# Spring12_6_rev4.net
KiCad netlist of a schematic drawn in EAGLE
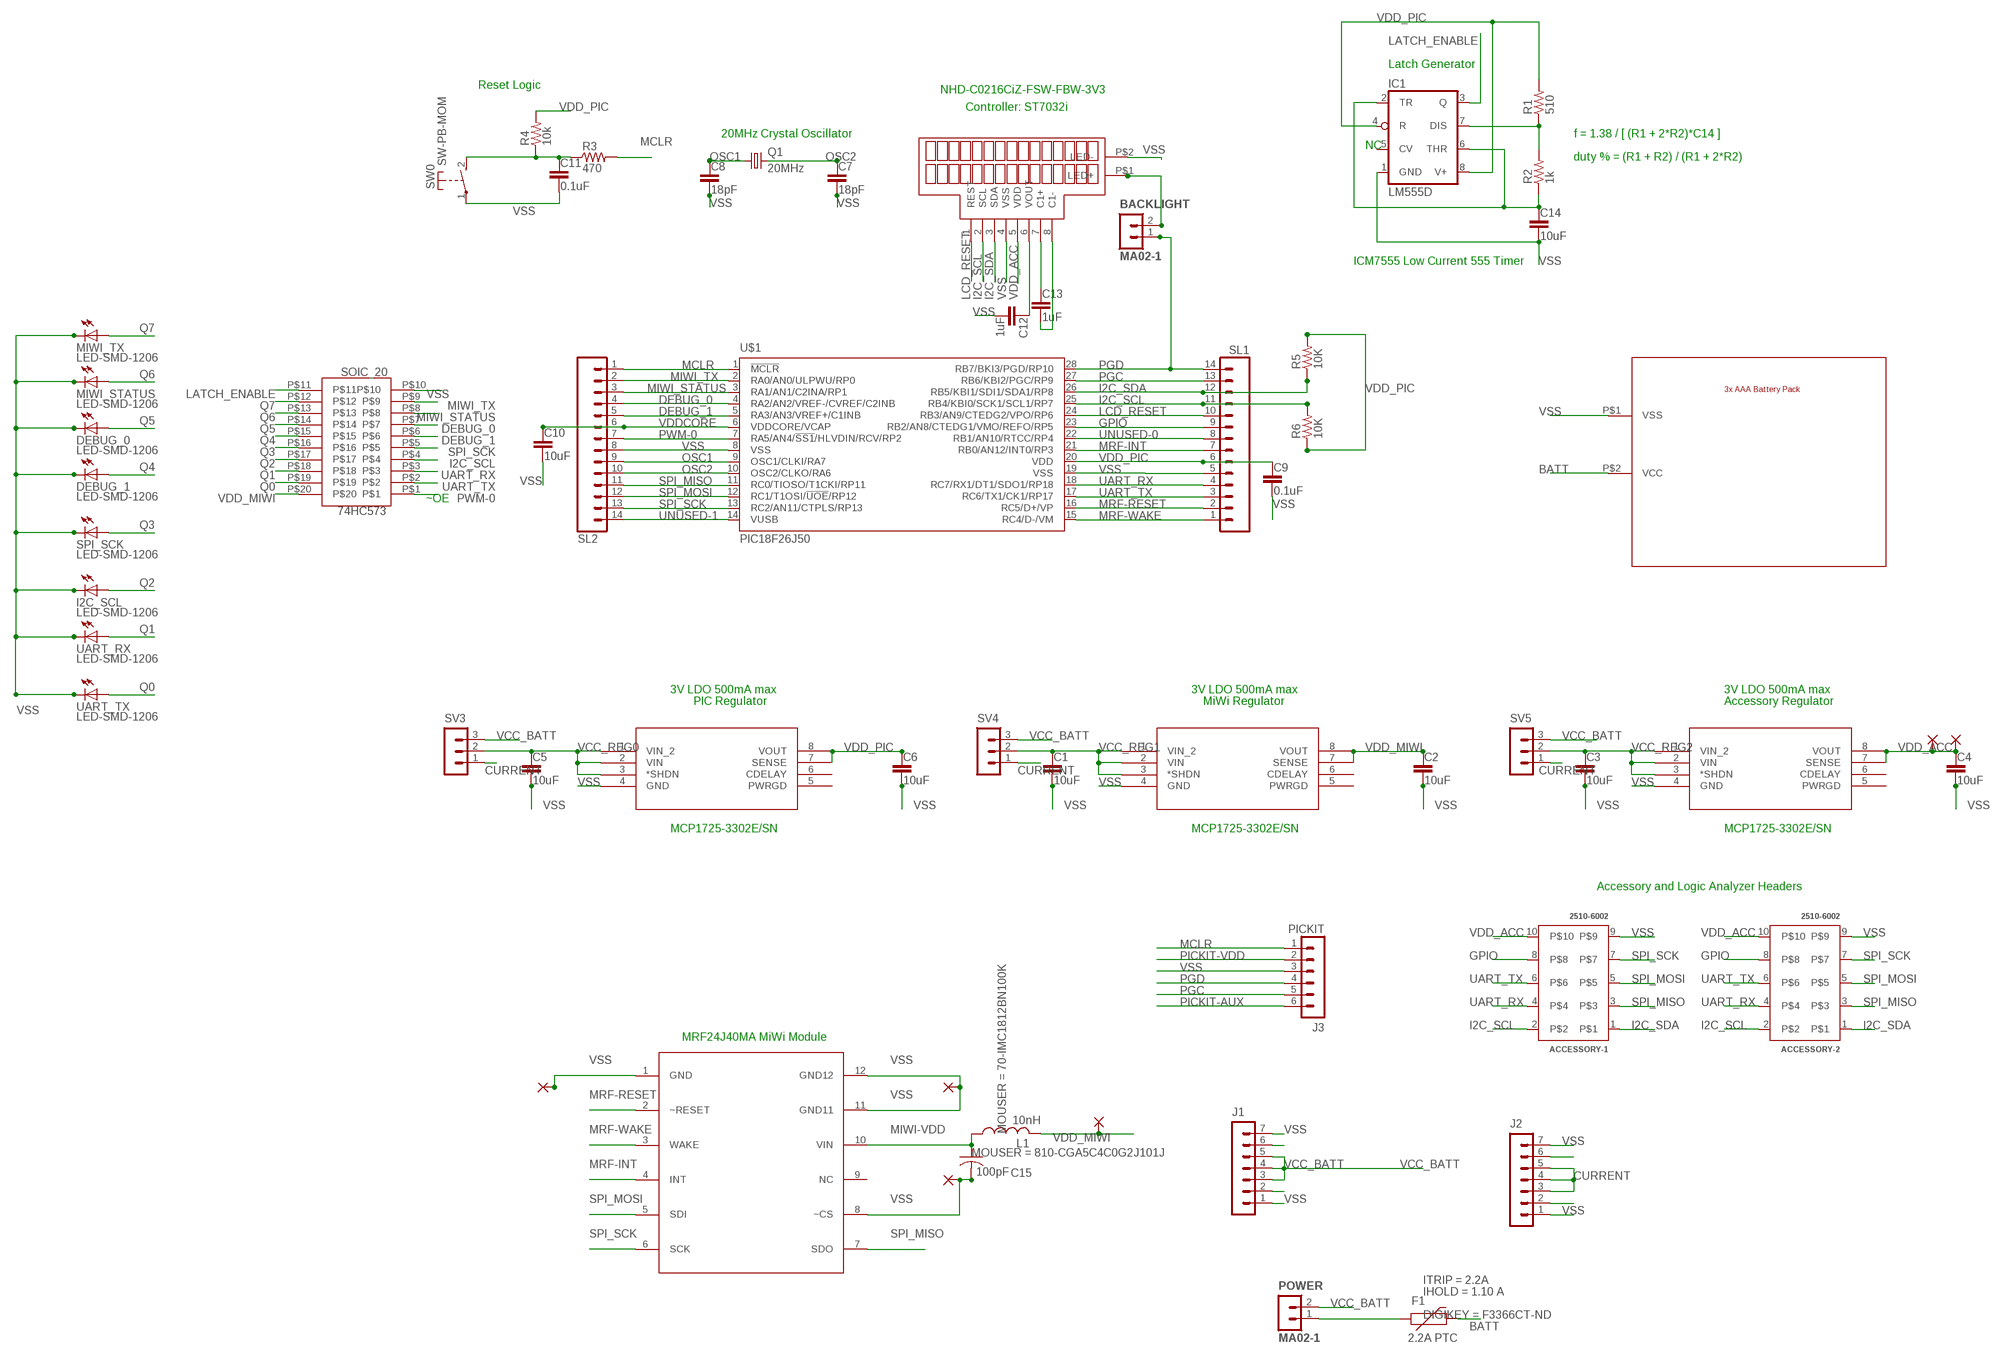
[diagram p0: schematic, sheet 1]

(export (version "E")
  (design (tool "Eeschema 10.0.6"))
  (components
    (comp (ref "74HC573")
      (value "SOIC_20")
      (footprint "eagle-import:SO20W")
      (libsource (lib "eagle-import") (part "SOIC_20"))
    )
    (comp (ref "ACCESSORY-1")
      (value "2510-6002")
      (footprint "eagle-import:2510-6002")
      (libsource (lib "eagle-import") (part "2510-6002"))
    )
    (comp (ref "ACCESSORY-2")
      (value "2510-6002")
      (footprint "eagle-import:2510-6002")
      (libsource (lib "eagle-import") (part "2510-6002"))
    )
    (comp (ref "BACKLIGHT")
      (value "MA02-1")
      (footprint "eagle-import:MA02-1")
      (libsource (lib "eagle-import") (part "MA02-1"))
    )
    (comp (ref "BATT0")
      (value "2479-BATTERY")
      (footprint "eagle-import:2479-BATTERY")
      (libsource (lib "eagle-import") (part "2479-BATTERY"))
    )
    (comp (ref "C1")
      (value "10uF")
      (footprint "eagle-import:C2.5-5")
      (libsource (lib "eagle-import") (part "C2.5-5"))
    )
    (comp (ref "C2")
      (value "10uF")
      (footprint "eagle-import:C2.5-5")
      (libsource (lib "eagle-import") (part "C2.5-5"))
    )
    (comp (ref "C3")
      (value "10uF")
      (footprint "eagle-import:C2.5-5")
      (libsource (lib "eagle-import") (part "C2.5-5"))
    )
    (comp (ref "C4")
      (value "10uF")
      (footprint "eagle-import:C2.5-5")
      (libsource (lib "eagle-import") (part "C2.5-5"))
    )
    (comp (ref "C5")
      (value "10uF")
      (footprint "eagle-import:C2.5-5")
      (libsource (lib "eagle-import") (part "C2.5-5"))
    )
    (comp (ref "C6")
      (value "10uF")
      (footprint "eagle-import:C2.5-5")
      (libsource (lib "eagle-import") (part "C2.5-5"))
    )
    (comp (ref "C7")
      (value "18pF")
      (footprint "eagle-import:C2.5-5")
      (libsource (lib "eagle-import") (part "C2.5-5"))
    )
    (comp (ref "C8")
      (value "18pF")
      (footprint "eagle-import:C2.5-5")
      (libsource (lib "eagle-import") (part "C2.5-5"))
    )
    (comp (ref "C9")
      (value "0.1uF")
      (footprint "eagle-import:C2.5-5")
      (libsource (lib "eagle-import") (part "C2.5-5"))
    )
    (comp (ref "C10")
      (value "10uF")
      (footprint "eagle-import:C2.5-5")
      (libsource (lib "eagle-import") (part "C2.5-5"))
    )
    (comp (ref "C11")
      (value "0.1uF")
      (footprint "eagle-import:C2.5-5")
      (libsource (lib "eagle-import") (part "C2.5-5"))
    )
    (comp (ref "C12")
      (value "1uF")
      (footprint "eagle-import:C2.5-5")
      (libsource (lib "eagle-import") (part "C2.5-5"))
    )
    (comp (ref "C13")
      (value "1uF")
      (footprint "eagle-import:C2.5-5")
      (libsource (lib "eagle-import") (part "C2.5-5"))
    )
    (comp (ref "C14")
      (value "10uF")
      (footprint "eagle-import:C2.5-5")
      (libsource (lib "eagle-import") (part "C2.5-5"))
    )
    (comp (ref "C15")
      (value "100pF")
      (footprint "eagle-import:C1206")
      (fields (field (name "MOUSER") "810-CGA5C4C0G2J101J"))
      (libsource (lib "eagle-import") (part "C-USC1206"))
    )
    (comp (ref "DEBUG_0")
      (value "LED-SMD-1206")
      (footprint "eagle-import:LED1206")
      (libsource (lib "eagle-import") (part "LED-SMD-1206"))
    )
    (comp (ref "DEBUG_1")
      (value "LED-SMD-1206")
      (footprint "eagle-import:LED1206")
      (libsource (lib "eagle-import") (part "LED-SMD-1206"))
    )
    (comp (ref "F1")
      (value "2.2A PTC")
      (footprint "eagle-import:PTC-1206")
      (fields
        (field (name "DIGIKEY") "F3366CT-ND")
        (field (name "IHOLD") "1.10 A")
        (field (name "ITRIP") "2.2A")
      )
      (libsource (lib "eagle-import") (part "PTCSMD"))
    )
    (comp (ref "I2C_SCL")
      (value "LED-SMD-1206")
      (footprint "eagle-import:LED1206")
      (libsource (lib "eagle-import") (part "LED-SMD-1206"))
    )
    (comp (ref "IC1")
      (value "LM555D")
      (footprint "eagle-import:SO08")
      (libsource (lib "eagle-import") (part "555DLM"))
    )
    (comp (ref "J1")
      (value "MA07-1")
      (footprint "eagle-import:MA07-1")
      (libsource (lib "eagle-import") (part "MA07-1"))
    )
    (comp (ref "J2")
      (value "MA07-1")
      (footprint "eagle-import:MA07-1")
      (libsource (lib "eagle-import") (part "MA07-1"))
    )
    (comp (ref "J3")
      (value "PICKIT")
      (footprint "eagle-import:MA06-1")
      (libsource (lib "eagle-import") (part "MA06-1"))
    )
    (comp (ref "L1")
      (value "10nH")
      (footprint "eagle-import:L1812")
      (fields (field (name "MOUSER") "70-IMC1812BN100K"))
      (libsource (lib "eagle-import") (part "L-USL1812"))
    )
    (comp (ref "MIWI_STATUS")
      (value "LED-SMD-1206")
      (footprint "eagle-import:LED1206")
      (libsource (lib "eagle-import") (part "LED-SMD-1206"))
    )
    (comp (ref "MIWI_TX")
      (value "LED-SMD-1206")
      (footprint "eagle-import:LED1206")
      (libsource (lib "eagle-import") (part "LED-SMD-1206"))
    )
    (comp (ref "POWER")
      (value "MA02-1")
      (footprint "eagle-import:MA02-1")
      (libsource (lib "eagle-import") (part "MA02-1"))
    )
    (comp (ref "Q1")
      (value "20MHz")
      (footprint "eagle-import:HC49U-V")
      (libsource (lib "eagle-import") (part "CRYSTALHC49U-V"))
    )
    (comp (ref "R1")
      (value "510")
      (footprint "eagle-import:R1206")
      (libsource (lib "eagle-import") (part "R1206"))
    )
    (comp (ref "R2")
      (value "1k")
      (footprint "eagle-import:R1206")
      (libsource (lib "eagle-import") (part "R1206"))
    )
    (comp (ref "R3")
      (value "470")
      (footprint "eagle-import:R1206")
      (libsource (lib "eagle-import") (part "R1206"))
    )
    (comp (ref "R4")
      (value "10k")
      (footprint "eagle-import:R1206")
      (libsource (lib "eagle-import") (part "R1206"))
    )
    (comp (ref "R5")
      (value "10K")
      (footprint "eagle-import:R1206")
      (libsource (lib "eagle-import") (part "R1206"))
    )
    (comp (ref "R6")
      (value "10K")
      (footprint "eagle-import:R1206")
      (libsource (lib "eagle-import") (part "R1206"))
    )
    (comp (ref "REG0")
      (value "MCP1725-XXXXX/SN")
      (footprint "eagle-import:SOIC8-N_MC")
      (libsource (lib "eagle-import") (part "MCP1725-XXXXX/SN"))
    )
    (comp (ref "REG1")
      (value "MCP1725-XXXXX/SN")
      (footprint "eagle-import:SOIC8-N_MC")
      (libsource (lib "eagle-import") (part "MCP1725-XXXXX/SN"))
    )
    (comp (ref "REG2")
      (value "MCP1725-XXXXX/SN")
      (footprint "eagle-import:SOIC8-N_MC")
      (libsource (lib "eagle-import") (part "MCP1725-XXXXX/SN"))
    )
    (comp (ref "RF0")
      (value "MRF24J40MA")
      (footprint "eagle-import:PCB12")
      (libsource (lib "eagle-import") (part "MRF24J40MA"))
    )
    (comp (ref "SL1")
      (value "M14")
      (footprint "eagle-import:14P")
      (libsource (lib "eagle-import") (part "M14"))
    )
    (comp (ref "SL2")
      (value "M14")
      (footprint "eagle-import:14P")
      (libsource (lib "eagle-import") (part "M14"))
    )
    (comp (ref "SPI_SCK")
      (value "LED-SMD-1206")
      (footprint "eagle-import:LED1206")
      (libsource (lib "eagle-import") (part "LED-SMD-1206"))
    )
    (comp (ref "SV3")
      (value "MA03-1")
      (footprint "eagle-import:MA03-1")
      (libsource (lib "eagle-import") (part "MA03-1"))
    )
    (comp (ref "SV4")
      (value "MA03-1")
      (footprint "eagle-import:MA03-1")
      (libsource (lib "eagle-import") (part "MA03-1"))
    )
    (comp (ref "SV5")
      (value "MA03-1")
      (footprint "eagle-import:MA03-1")
      (libsource (lib "eagle-import") (part "MA03-1"))
    )
    (comp (ref "SW0")
      (value "SW-PB-MOM")
      (footprint "eagle-import:SW-MOM-PB")
      (libsource (lib "eagle-import") (part "SW-PB-MOM"))
    )
    (comp (ref "U$1")
      (value "PIC18F26J50")
      (footprint "eagle-import:DIL28-3")
      (libsource (lib "eagle-import") (part "PIC18F26J50"))
    )
    (comp (ref "U$2")
      (value "NHD-C0216CIZ-FSW-FBW-3V3")
      (footprint "eagle-import:SIL8-1.5")
      (libsource (lib "eagle-import") (part "NHD-C0216CIZ-FN-FBW-3V"))
    )
    (comp (ref "U$3")
      (value "VIA")
      (footprint "eagle-import:VIA")
      (libsource (lib "eagle-import") (part "VIA"))
    )
    (comp (ref "U$4")
      (value "VIA")
      (footprint "eagle-import:VIA")
      (libsource (lib "eagle-import") (part "VIA"))
    )
    (comp (ref "U$5")
      (value "VIA")
      (footprint "eagle-import:VIA")
      (libsource (lib "eagle-import") (part "VIA"))
    )
    (comp (ref "U$18")
      (value "VIA")
      (footprint "eagle-import:VIA")
      (libsource (lib "eagle-import") (part "VIA"))
    )
    (comp (ref "U$19")
      (value "VIA")
      (footprint "eagle-import:VIA")
      (libsource (lib "eagle-import") (part "VIA"))
    )
    (comp (ref "U$20")
      (value "VIA")
      (footprint "eagle-import:VIA")
      (libsource (lib "eagle-import") (part "VIA"))
    )
    (comp (ref "UART_RX")
      (value "LED-SMD-1206")
      (footprint "eagle-import:LED1206")
      (libsource (lib "eagle-import") (part "LED-SMD-1206"))
    )
    (comp (ref "UART_TX")
      (value "LED-SMD-1206")
      (footprint "eagle-import:LED1206")
      (libsource (lib "eagle-import") (part "LED-SMD-1206"))
    )
  )
  (nets
    (net (code "1") (name "/BATT") (class "Default")
      (node (ref "BATT0") (pin "P$2") (pinfunction "VCC_P$2") (pintype "bidirectional"))
      (node (ref "F1") (pin "2") (pinfunction "2_2") (pintype "bidirectional"))
    )
    (net (code "2") (name "/CURRENT") (class "Default")
      (node (ref "J2") (pin "3") (pinfunction "3_3") (pintype "passive"))
      (node (ref "J2") (pin "4") (pinfunction "4_4") (pintype "passive"))
      (node (ref "J2") (pin "5") (pinfunction "5_5") (pintype "passive"))
      (node (ref "SV3") (pin "1") (pinfunction "1_1") (pintype "passive"))
      (node (ref "SV4") (pin "1") (pinfunction "1_1") (pintype "passive"))
      (node (ref "SV5") (pin "1") (pinfunction "1_1") (pintype "passive"))
    )
    (net (code "3") (name "/DEBUG_0") (class "Default")
      (node (ref "74HC573") (pin "P$7") (pinfunction "P$7_P$7") (pintype "bidirectional"))
      (node (ref "SL2") (pin "4") (pinfunction "4_4") (pintype "passive"))
      (node (ref "U$1") (pin "4") (pinfunction "RA2/AN2/VREF-/CVREF/C2INB_4") (pintype "bidirectional"))
    )
    (net (code "4") (name "/DEBUG_1") (class "Default")
      (node (ref "74HC573") (pin "P$6") (pinfunction "P$6_P$6") (pintype "bidirectional"))
      (node (ref "SL2") (pin "5") (pinfunction "5_5") (pintype "passive"))
      (node (ref "U$1") (pin "5") (pinfunction "RA3/AN3/VREF+/C1INB_5") (pintype "bidirectional"))
    )
    (net (code "5") (name "/GPIO") (class "Default")
      (node (ref "ACCESSORY-1") (pin "8") (pinfunction "P$8_8") (pintype "passive"))
      (node (ref "ACCESSORY-2") (pin "8") (pinfunction "P$8_8") (pintype "passive"))
      (node (ref "SL1") (pin "9") (pinfunction "9_9") (pintype "passive"))
      (node (ref "U$1") (pin "23") (pinfunction "RB2/AN8/CTEDG1/VMO/REFO/RP5_23") (pintype "bidirectional"))
    )
    (net (code "6") (name "/I2C_SCL") (class "Default")
      (node (ref "74HC573") (pin "P$4") (pinfunction "P$4_P$4") (pintype "bidirectional"))
      (node (ref "ACCESSORY-1") (pin "2") (pinfunction "P$2_2") (pintype "passive"))
      (node (ref "ACCESSORY-2") (pin "2") (pinfunction "P$2_2") (pintype "passive"))
      (node (ref "R6") (pin "2") (pinfunction "2_2") (pintype "passive"))
      (node (ref "SL1") (pin "11") (pinfunction "11_11") (pintype "passive"))
      (node (ref "U$1") (pin "25") (pinfunction "RB4/KBI0/SCK1/SCL1/RP7_25") (pintype "bidirectional"))
      (node (ref "U$2") (pin "2") (pinfunction "SCL_2") (pintype "bidirectional"))
    )
    (net (code "7") (name "/I2C_SDA") (class "Default")
      (node (ref "ACCESSORY-1") (pin "1") (pinfunction "P$1_1") (pintype "passive"))
      (node (ref "ACCESSORY-2") (pin "1") (pinfunction "P$1_1") (pintype "passive"))
      (node (ref "R5") (pin "1") (pinfunction "1_1") (pintype "passive"))
      (node (ref "SL1") (pin "12") (pinfunction "12_12") (pintype "passive"))
      (node (ref "U$1") (pin "26") (pinfunction "RB5/KBI1/SDI1/SDA1/RP8_26") (pintype "bidirectional"))
      (node (ref "U$2") (pin "3") (pinfunction "SDA_3") (pintype "bidirectional"))
    )
    (net (code "8") (name "/LATCH_ENABLE") (class "Default")
      (node (ref "74HC573") (pin "P$11") (pinfunction "P$11_P$11") (pintype "bidirectional"))
      (node (ref "IC1") (pin "3") (pinfunction "Q_3") (pintype "output"))
    )
    (net (code "9") (name "/LCD_RESET") (class "Default")
      (node (ref "SL1") (pin "10") (pinfunction "10_10") (pintype "passive"))
      (node (ref "U$1") (pin "24") (pinfunction "RB3/AN9/CTEDG2/VPO/RP6_24") (pintype "bidirectional"))
      (node (ref "U$2") (pin "1") (pinfunction "REST_1") (pintype "bidirectional"))
    )
    (net (code "10") (name "/MCLR") (class "Default")
      (node (ref "J3") (pin "1") (pinfunction "1_1") (pintype "passive"))
      (node (ref "R3") (pin "2") (pinfunction "2_2") (pintype "passive"))
      (node (ref "SL2") (pin "1") (pinfunction "1_1") (pintype "passive"))
      (node (ref "U$1") (pin "1") (pinfunction "~{MCLR}_1") (pintype "input"))
    )
    (net (code "11") (name "/MIWI-VDD") (class "Default")
      (node (ref "C15") (pin "1") (pinfunction "1_1") (pintype "passive"))
      (node (ref "L1") (pin "1") (pinfunction "1_1") (pintype "passive"))
      (node (ref "RF0") (pin "10") (pinfunction "VIN_10") (pintype "bidirectional"))
    )
    (net (code "12") (name "/MIWI_STATUS") (class "Default")
      (node (ref "74HC573") (pin "P$8") (pinfunction "P$8_P$8") (pintype "bidirectional"))
      (node (ref "SL2") (pin "3") (pinfunction "3_3") (pintype "passive"))
      (node (ref "U$1") (pin "3") (pinfunction "RA1/AN1/C2INA/RP1_3") (pintype "bidirectional"))
    )
    (net (code "13") (name "/MIWI_TX") (class "Default")
      (node (ref "74HC573") (pin "P$9") (pinfunction "P$9_P$9") (pintype "bidirectional"))
      (node (ref "SL2") (pin "2") (pinfunction "2_2") (pintype "passive"))
      (node (ref "U$1") (pin "2") (pinfunction "RA0/AN0/ULPWU/RP0_2") (pintype "bidirectional"))
    )
    (net (code "14") (name "/MRF-INT") (class "Default")
      (node (ref "RF0") (pin "4") (pinfunction "INT_4") (pintype "bidirectional"))
      (node (ref "SL1") (pin "7") (pinfunction "7_7") (pintype "passive"))
      (node (ref "U$1") (pin "21") (pinfunction "RB0/AN12/INT0/RP3_21") (pintype "bidirectional"))
    )
    (net (code "15") (name "/MRF-RESET") (class "Default")
      (node (ref "RF0") (pin "2") (pinfunction "~{RESET}_2") (pintype "bidirectional"))
      (node (ref "SL1") (pin "2") (pinfunction "2_2") (pintype "passive"))
      (node (ref "U$1") (pin "16") (pinfunction "RC5/D+/VP_16") (pintype "bidirectional"))
    )
    (net (code "16") (name "/MRF-WAKE") (class "Default")
      (node (ref "RF0") (pin "3") (pinfunction "WAKE_3") (pintype "bidirectional"))
      (node (ref "SL1") (pin "1") (pinfunction "1_1") (pintype "passive"))
      (node (ref "U$1") (pin "15") (pinfunction "RC4/D-/VM_15") (pintype "bidirectional"))
    )
    (net (code "17") (name "/OSC1") (class "Default")
      (node (ref "C8") (pin "1") (pinfunction "1_1") (pintype "passive"))
      (node (ref "Q1") (pin "1") (pinfunction "1_1") (pintype "passive"))
      (node (ref "SL2") (pin "9") (pinfunction "9_9") (pintype "passive"))
      (node (ref "U$1") (pin "9") (pinfunction "OSC1/CLKI/RA7_9") (pintype "input"))
    )
    (net (code "18") (name "/OSC2") (class "Default")
      (node (ref "C7") (pin "1") (pinfunction "1_1") (pintype "passive"))
      (node (ref "Q1") (pin "2") (pinfunction "2_2") (pintype "passive"))
      (node (ref "SL2") (pin "10") (pinfunction "10_10") (pintype "passive"))
      (node (ref "U$1") (pin "10") (pinfunction "OSC2/CLKO/RA6_10") (pintype "output"))
    )
    (net (code "19") (name "/PGC") (class "Default")
      (node (ref "J3") (pin "5") (pinfunction "5_5") (pintype "passive"))
      (node (ref "SL1") (pin "13") (pinfunction "13_13") (pintype "passive"))
      (node (ref "U$1") (pin "27") (pinfunction "RB6/KBI2/PGC/RP9_27") (pintype "bidirectional"))
    )
    (net (code "20") (name "/PGD") (class "Default")
      (node (ref "BACKLIGHT") (pin "1") (pinfunction "1_1") (pintype "passive"))
      (node (ref "J3") (pin "4") (pinfunction "4_4") (pintype "passive"))
      (node (ref "SL1") (pin "14") (pinfunction "14_14") (pintype "passive"))
      (node (ref "U$1") (pin "28") (pinfunction "RB7/BKI3/PGD/RP10_28") (pintype "bidirectional"))
    )
    (net (code "21") (name "/PICKIT-AUX") (class "Default")
      (node (ref "J3") (pin "6") (pinfunction "6_6") (pintype "passive"))
    )
    (net (code "22") (name "/PICKIT-VDD") (class "Default")
      (node (ref "J3") (pin "2") (pinfunction "2_2") (pintype "passive"))
    )
    (net (code "23") (name "/PWM-0") (class "Default")
      (node (ref "74HC573") (pin "P$1") (pinfunction "P$1_P$1") (pintype "bidirectional"))
      (node (ref "SL2") (pin "7") (pinfunction "7_7") (pintype "passive"))
      (node (ref "U$1") (pin "7") (pinfunction "RA5/AN4/~{SS1}/HLVDIN/RCV/RP2_7") (pintype "bidirectional"))
    )
    (net (code "24") (name "/Q0") (class "Default")
      (node (ref "74HC573") (pin "P$19") (pinfunction "P$19_P$19") (pintype "bidirectional"))
      (node (ref "UART_TX") (pin "A") (pinfunction "A_A") (pintype "passive"))
    )
    (net (code "25") (name "/Q1") (class "Default")
      (node (ref "74HC573") (pin "P$18") (pinfunction "P$18_P$18") (pintype "bidirectional"))
      (node (ref "UART_RX") (pin "A") (pinfunction "A_A") (pintype "passive"))
    )
    (net (code "26") (name "/Q2") (class "Default")
      (node (ref "74HC573") (pin "P$17") (pinfunction "P$17_P$17") (pintype "bidirectional"))
      (node (ref "I2C_SCL") (pin "A") (pinfunction "A_A") (pintype "passive"))
    )
    (net (code "27") (name "/Q3") (class "Default")
      (node (ref "74HC573") (pin "P$16") (pinfunction "P$16_P$16") (pintype "bidirectional"))
      (node (ref "SPI_SCK") (pin "A") (pinfunction "A_A") (pintype "passive"))
    )
    (net (code "28") (name "/Q4") (class "Default")
      (node (ref "74HC573") (pin "P$15") (pinfunction "P$15_P$15") (pintype "bidirectional"))
      (node (ref "DEBUG_1") (pin "A") (pinfunction "A_A") (pintype "passive"))
    )
    (net (code "29") (name "/Q5") (class "Default")
      (node (ref "74HC573") (pin "P$14") (pinfunction "P$14_P$14") (pintype "bidirectional"))
      (node (ref "DEBUG_0") (pin "A") (pinfunction "A_A") (pintype "passive"))
    )
    (net (code "30") (name "/Q6") (class "Default")
      (node (ref "74HC573") (pin "P$13") (pinfunction "P$13_P$13") (pintype "bidirectional"))
      (node (ref "MIWI_STATUS") (pin "A") (pinfunction "A_A") (pintype "passive"))
    )
    (net (code "31") (name "/Q7") (class "Default")
      (node (ref "74HC573") (pin "P$12") (pinfunction "P$12_P$12") (pintype "bidirectional"))
      (node (ref "MIWI_TX") (pin "A") (pinfunction "A_A") (pintype "passive"))
    )
    (net (code "32") (name "/SPI_MISO") (class "Default")
      (node (ref "ACCESSORY-1") (pin "3") (pinfunction "P$3_3") (pintype "passive"))
      (node (ref "ACCESSORY-2") (pin "3") (pinfunction "P$3_3") (pintype "passive"))
      (node (ref "RF0") (pin "7") (pinfunction "SDO_7") (pintype "bidirectional"))
      (node (ref "SL2") (pin "11") (pinfunction "11_11") (pintype "passive"))
      (node (ref "U$1") (pin "11") (pinfunction "RC0/TIOSO/T1CKI/RP11_11") (pintype "bidirectional"))
    )
    (net (code "33") (name "/SPI_MOSI") (class "Default")
      (node (ref "ACCESSORY-1") (pin "5") (pinfunction "P$5_5") (pintype "passive"))
      (node (ref "ACCESSORY-2") (pin "5") (pinfunction "P$5_5") (pintype "passive"))
      (node (ref "RF0") (pin "5") (pinfunction "SDI_5") (pintype "bidirectional"))
      (node (ref "SL2") (pin "12") (pinfunction "12_12") (pintype "passive"))
      (node (ref "U$1") (pin "12") (pinfunction "RC1/T1OSI/~{UOE}/RP12_12") (pintype "bidirectional"))
    )
    (net (code "34") (name "/SPI_SCK") (class "Default")
      (node (ref "74HC573") (pin "P$5") (pinfunction "P$5_P$5") (pintype "bidirectional"))
      (node (ref "ACCESSORY-1") (pin "7") (pinfunction "P$7_7") (pintype "passive"))
      (node (ref "ACCESSORY-2") (pin "7") (pinfunction "P$7_7") (pintype "passive"))
      (node (ref "RF0") (pin "6") (pinfunction "SCK_6") (pintype "bidirectional"))
      (node (ref "SL2") (pin "13") (pinfunction "13_13") (pintype "passive"))
      (node (ref "U$1") (pin "13") (pinfunction "RC2/AN11/CTPLS/RP13_13") (pintype "bidirectional"))
    )
    (net (code "35") (name "/UART_RX") (class "Default")
      (node (ref "74HC573") (pin "P$3") (pinfunction "P$3_P$3") (pintype "bidirectional"))
      (node (ref "ACCESSORY-1") (pin "4") (pinfunction "P$4_4") (pintype "passive"))
      (node (ref "ACCESSORY-2") (pin "4") (pinfunction "P$4_4") (pintype "passive"))
      (node (ref "SL1") (pin "4") (pinfunction "4_4") (pintype "passive"))
      (node (ref "U$1") (pin "18") (pinfunction "RC7/RX1/DT1/SDO1/RP18_18") (pintype "bidirectional"))
    )
    (net (code "36") (name "/UART_TX") (class "Default")
      (node (ref "74HC573") (pin "P$2") (pinfunction "P$2_P$2") (pintype "bidirectional"))
      (node (ref "ACCESSORY-1") (pin "6") (pinfunction "P$6_6") (pintype "passive"))
      (node (ref "ACCESSORY-2") (pin "6") (pinfunction "P$6_6") (pintype "passive"))
      (node (ref "SL1") (pin "3") (pinfunction "3_3") (pintype "passive"))
      (node (ref "U$1") (pin "17") (pinfunction "RC6/TX1/CK1/RP17_17") (pintype "bidirectional"))
    )
    (net (code "37") (name "/UNUSED-0") (class "Default")
      (node (ref "SL1") (pin "8") (pinfunction "8_8") (pintype "passive"))
      (node (ref "U$1") (pin "22") (pinfunction "RB1/AN10/RTCC/RP4_22") (pintype "bidirectional"))
    )
    (net (code "38") (name "/UNUSED-1") (class "Default")
      (node (ref "SL2") (pin "14") (pinfunction "14_14") (pintype "passive"))
      (node (ref "U$1") (pin "14") (pinfunction "VUSB_14") (pintype "bidirectional"))
    )
    (net (code "39") (name "/VCC_BATT") (class "Default")
      (node (ref "J1") (pin "3") (pinfunction "3_3") (pintype "passive"))
      (node (ref "J1") (pin "4") (pinfunction "4_4") (pintype "passive"))
      (node (ref "J1") (pin "5") (pinfunction "5_5") (pintype "passive"))
      (node (ref "POWER") (pin "2") (pinfunction "2_2") (pintype "passive"))
      (node (ref "SV3") (pin "3") (pinfunction "3_3") (pintype "passive"))
      (node (ref "SV4") (pin "3") (pinfunction "3_3") (pintype "passive"))
      (node (ref "SV5") (pin "3") (pinfunction "3_3") (pintype "passive"))
    )
    (net (code "40") (name "/VCC_REG0") (class "Default")
      (node (ref "C5") (pin "1") (pinfunction "1_1") (pintype "passive"))
      (node (ref "REG0") (pin "1") (pinfunction "VIN_2_1") (pintype "passive"))
      (node (ref "REG0") (pin "2") (pinfunction "VIN_2") (pintype "passive"))
      (node (ref "REG0") (pin "3") (pinfunction "*SHDN_3") (pintype "passive"))
      (node (ref "SV3") (pin "2") (pinfunction "2_2") (pintype "passive"))
    )
    (net (code "41") (name "/VCC_REG1") (class "Default")
      (node (ref "C1") (pin "1") (pinfunction "1_1") (pintype "passive"))
      (node (ref "REG1") (pin "1") (pinfunction "VIN_2_1") (pintype "passive"))
      (node (ref "REG1") (pin "2") (pinfunction "VIN_2") (pintype "passive"))
      (node (ref "REG1") (pin "3") (pinfunction "*SHDN_3") (pintype "passive"))
      (node (ref "SV4") (pin "2") (pinfunction "2_2") (pintype "passive"))
    )
    (net (code "42") (name "/VCC_REG2") (class "Default")
      (node (ref "C3") (pin "1") (pinfunction "1_1") (pintype "passive"))
      (node (ref "REG2") (pin "1") (pinfunction "VIN_2_1") (pintype "passive"))
      (node (ref "REG2") (pin "2") (pinfunction "VIN_2") (pintype "passive"))
      (node (ref "REG2") (pin "3") (pinfunction "*SHDN_3") (pintype "passive"))
      (node (ref "SV5") (pin "2") (pinfunction "2_2") (pintype "passive"))
    )
    (net (code "43") (name "/VDDCORE") (class "Default")
      (node (ref "C10") (pin "1") (pinfunction "1_1") (pintype "passive"))
      (node (ref "SL2") (pin "6") (pinfunction "6_6") (pintype "passive"))
      (node (ref "U$1") (pin "6") (pinfunction "VDDCORE/VCAP_6") (pintype "input"))
    )
    (net (code "44") (name "/VDD_ACC") (class "Default")
      (node (ref "ACCESSORY-1") (pin "10") (pinfunction "P$10_10") (pintype "passive"))
      (node (ref "ACCESSORY-2") (pin "10") (pinfunction "P$10_10") (pintype "passive"))
      (node (ref "C4") (pin "1") (pinfunction "1_1") (pintype "passive"))
      (node (ref "REG2") (pin "7") (pinfunction "SENSE_7") (pintype "passive"))
      (node (ref "REG2") (pin "8") (pinfunction "VOUT_8") (pintype "passive"))
      (node (ref "U$2") (pin "5") (pinfunction "VDD_5") (pintype "power_in"))
      (node (ref "U$3") (pin "1") (pinfunction "P_1") (pintype "passive"))
      (node (ref "U$4") (pin "1") (pinfunction "P_1") (pintype "passive"))
    )
    (net (code "45") (name "/VDD_MIWI") (class "Default")
      (node (ref "74HC573") (pin "P$20") (pinfunction "P$20_P$20") (pintype "bidirectional"))
      (node (ref "C2") (pin "1") (pinfunction "1_1") (pintype "passive"))
      (node (ref "L1") (pin "2") (pinfunction "2_2") (pintype "passive"))
      (node (ref "REG1") (pin "7") (pinfunction "SENSE_7") (pintype "passive"))
      (node (ref "REG1") (pin "8") (pinfunction "VOUT_8") (pintype "passive"))
      (node (ref "U$5") (pin "1") (pinfunction "P_1") (pintype "passive"))
    )
    (net (code "46") (name "/VDD_PIC") (class "Default")
      (node (ref "C6") (pin "1") (pinfunction "1_1") (pintype "passive"))
      (node (ref "C9") (pin "1") (pinfunction "1_1") (pintype "passive"))
      (node (ref "IC1") (pin "4") (pinfunction "R_4") (pintype "input"))
      (node (ref "IC1") (pin "8") (pinfunction "V+_8") (pintype "power_in"))
      (node (ref "R1") (pin "2") (pinfunction "2_2") (pintype "passive"))
      (node (ref "R4") (pin "2") (pinfunction "2_2") (pintype "passive"))
      (node (ref "R5") (pin "2") (pinfunction "2_2") (pintype "passive"))
      (node (ref "R6") (pin "1") (pinfunction "1_1") (pintype "passive"))
      (node (ref "REG0") (pin "7") (pinfunction "SENSE_7") (pintype "passive"))
      (node (ref "REG0") (pin "8") (pinfunction "VOUT_8") (pintype "passive"))
      (node (ref "SL1") (pin "6") (pinfunction "6_6") (pintype "passive"))
      (node (ref "U$1") (pin "20") (pinfunction "VDD_20") (pintype "power_in"))
    )
    (net (code "47") (name "/VSS") (class "Default")
      (node (ref "74HC573") (pin "P$10") (pinfunction "P$10_P$10") (pintype "bidirectional"))
      (node (ref "ACCESSORY-1") (pin "9") (pinfunction "P$9_9") (pintype "passive"))
      (node (ref "ACCESSORY-2") (pin "9") (pinfunction "P$9_9") (pintype "passive"))
      (node (ref "BATT0") (pin "P$1") (pinfunction "VSS_P$1") (pintype "bidirectional"))
      (node (ref "C1") (pin "2") (pinfunction "2_2") (pintype "passive"))
      (node (ref "C10") (pin "2") (pinfunction "2_2") (pintype "passive"))
      (node (ref "C11") (pin "2") (pinfunction "2_2") (pintype "passive"))
      (node (ref "C12") (pin "2") (pinfunction "2_2") (pintype "passive"))
      (node (ref "C14") (pin "2") (pinfunction "2_2") (pintype "passive"))
      (node (ref "C15") (pin "2") (pinfunction "2_2") (pintype "passive"))
      (node (ref "C2") (pin "2") (pinfunction "2_2") (pintype "passive"))
      (node (ref "C3") (pin "2") (pinfunction "2_2") (pintype "passive"))
      (node (ref "C4") (pin "2") (pinfunction "2_2") (pintype "passive"))
      (node (ref "C5") (pin "2") (pinfunction "2_2") (pintype "passive"))
      (node (ref "C6") (pin "2") (pinfunction "2_2") (pintype "passive"))
      (node (ref "C7") (pin "2") (pinfunction "2_2") (pintype "passive"))
      (node (ref "C8") (pin "2") (pinfunction "2_2") (pintype "passive"))
      (node (ref "C9") (pin "2") (pinfunction "2_2") (pintype "passive"))
      (node (ref "DEBUG_0") (pin "C") (pinfunction "C_C") (pintype "passive"))
      (node (ref "DEBUG_1") (pin "C") (pinfunction "C_C") (pintype "passive"))
      (node (ref "I2C_SCL") (pin "C") (pinfunction "C_C") (pintype "passive"))
      (node (ref "IC1") (pin "1") (pinfunction "GND_1") (pintype "power_in"))
      (node (ref "J1") (pin "1") (pinfunction "1_1") (pintype "passive"))
      (node (ref "J1") (pin "7") (pinfunction "7_7") (pintype "passive"))
      (node (ref "J2") (pin "1") (pinfunction "1_1") (pintype "passive"))
      (node (ref "J2") (pin "7") (pinfunction "7_7") (pintype "passive"))
      (node (ref "J3") (pin "3") (pinfunction "3_3") (pintype "passive"))
      (node (ref "MIWI_STATUS") (pin "C") (pinfunction "C_C") (pintype "passive"))
      (node (ref "MIWI_TX") (pin "C") (pinfunction "C_C") (pintype "passive"))
      (node (ref "REG0") (pin "4") (pinfunction "GND_4") (pintype "passive"))
      (node (ref "REG1") (pin "4") (pinfunction "GND_4") (pintype "passive"))
      (node (ref "REG2") (pin "4") (pinfunction "GND_4") (pintype "passive"))
      (node (ref "RF0") (pin "1") (pinfunction "GND_1") (pintype "bidirectional"))
      (node (ref "RF0") (pin "11") (pinfunction "GND11_11") (pintype "bidirectional"))
      (node (ref "RF0") (pin "12") (pinfunction "GND12_12") (pintype "bidirectional"))
      (node (ref "RF0") (pin "8") (pinfunction "~{CS}_8") (pintype "bidirectional"))
      (node (ref "SL1") (pin "5") (pinfunction "5_5") (pintype "passive"))
      (node (ref "SL2") (pin "8") (pinfunction "8_8") (pintype "passive"))
      (node (ref "SPI_SCK") (pin "C") (pinfunction "C_C") (pintype "passive"))
      (node (ref "SW0") (pin "1") (pinfunction "P_1") (pintype "passive"))
      (node (ref "U$1") (pin "19") (pinfunction "VSS_19") (pintype "power_in"))
      (node (ref "U$1") (pin "8") (pinfunction "VSS_8") (pintype "power_in"))
      (node (ref "U$18") (pin "1") (pinfunction "P_1") (pintype "passive"))
      (node (ref "U$19") (pin "1") (pinfunction "P_1") (pintype "passive"))
      (node (ref "U$2") (pin "4") (pinfunction "VSS_4") (pintype "power_in"))
      (node (ref "U$2") (pin "P$2") (pinfunction "LED-_P$2") (pintype "power_in"))
      (node (ref "U$20") (pin "1") (pinfunction "P_1") (pintype "passive"))
      (node (ref "UART_RX") (pin "C") (pinfunction "C_C") (pintype "passive"))
      (node (ref "UART_TX") (pin "C") (pinfunction "C_C") (pintype "passive"))
    )
    (net (code "48") (name "Net-(F1-Pad1)") (class "Default")
      (node (ref "F1") (pin "1") (pinfunction "1_1") (pintype "bidirectional"))
      (node (ref "POWER") (pin "1") (pinfunction "1_1") (pintype "passive"))
    )
    (net (code "49") (name "Net-(IC1-DIS)") (class "Default")
      (node (ref "IC1") (pin "7") (pinfunction "DIS_7") (pintype "input"))
      (node (ref "R1") (pin "1") (pinfunction "1_1") (pintype "passive"))
      (node (ref "R2") (pin "2") (pinfunction "2_2") (pintype "passive"))
    )
    (net (code "50") (name "Net-(IC1-THR)") (class "Default")
      (node (ref "C14") (pin "1") (pinfunction "1_1") (pintype "passive"))
      (node (ref "IC1") (pin "2") (pinfunction "TR_2") (pintype "input"))
      (node (ref "IC1") (pin "6") (pinfunction "THR_6") (pintype "input"))
      (node (ref "R2") (pin "1") (pinfunction "1_1") (pintype "passive"))
    )
    (net (code "51") (name "Net-(SW0-S)") (class "Default")
      (node (ref "C11") (pin "1") (pinfunction "1_1") (pintype "passive"))
      (node (ref "R3") (pin "1") (pinfunction "1_1") (pintype "passive"))
      (node (ref "R4") (pin "1") (pinfunction "1_1") (pintype "passive"))
      (node (ref "SW0") (pin "2") (pinfunction "S_2") (pintype "passive"))
    )
    (net (code "52") (name "Net-(U$2-C1+)") (class "Default")
      (node (ref "C13") (pin "1") (pinfunction "1_1") (pintype "passive"))
      (node (ref "U$2") (pin "7") (pinfunction "C1+_7") (pintype "bidirectional"))
    )
    (net (code "53") (name "Net-(U$2-C1-)") (class "Default")
      (node (ref "C13") (pin "2") (pinfunction "2_2") (pintype "passive"))
      (node (ref "U$2") (pin "8") (pinfunction "C1-_8") (pintype "bidirectional"))
    )
    (net (code "54") (name "Net-(U$2-LED+)") (class "Default")
      (node (ref "BACKLIGHT") (pin "2") (pinfunction "2_2") (pintype "passive"))
      (node (ref "U$2") (pin "P$1") (pinfunction "LED+_P$1") (pintype "power_in"))
    )
    (net (code "55") (name "Net-(U$2-VOUT)") (class "Default")
      (node (ref "C12") (pin "1") (pinfunction "1_1") (pintype "passive"))
      (node (ref "U$2") (pin "6") (pinfunction "VOUT_6") (pintype "output"))
    )
    (net (code "56") (name "unconnected-(IC1-CV-Pad5)") (class "Default")
      (node (ref "IC1") (pin "5") (pinfunction "CV_5") (pintype "input"))
    )
    (net (code "57") (name "unconnected-(J1-Pad2)") (class "Default")
      (node (ref "J1") (pin "2") (pinfunction "2_2") (pintype "passive"))
    )
    (net (code "58") (name "unconnected-(J1-Pad6)") (class "Default")
      (node (ref "J1") (pin "6") (pinfunction "6_6") (pintype "passive"))
    )
    (net (code "59") (name "unconnected-(J2-Pad2)") (class "Default")
      (node (ref "J2") (pin "2") (pinfunction "2_2") (pintype "passive"))
    )
    (net (code "60") (name "unconnected-(J2-Pad6)") (class "Default")
      (node (ref "J2") (pin "6") (pinfunction "6_6") (pintype "passive"))
    )
    (net (code "61") (name "unconnected-(REG0-CDELAY-Pad6)") (class "Default")
      (node (ref "REG0") (pin "6") (pinfunction "CDELAY_6") (pintype "passive"))
    )
    (net (code "62") (name "unconnected-(REG0-PWRGD-Pad5)") (class "Default")
      (node (ref "REG0") (pin "5") (pinfunction "PWRGD_5") (pintype "passive"))
    )
    (net (code "63") (name "unconnected-(REG1-CDELAY-Pad6)") (class "Default")
      (node (ref "REG1") (pin "6") (pinfunction "CDELAY_6") (pintype "passive"))
    )
    (net (code "64") (name "unconnected-(REG1-PWRGD-Pad5)") (class "Default")
      (node (ref "REG1") (pin "5") (pinfunction "PWRGD_5") (pintype "passive"))
    )
    (net (code "65") (name "unconnected-(REG2-CDELAY-Pad6)") (class "Default")
      (node (ref "REG2") (pin "6") (pinfunction "CDELAY_6") (pintype "passive"))
    )
    (net (code "66") (name "unconnected-(REG2-PWRGD-Pad5)") (class "Default")
      (node (ref "REG2") (pin "5") (pinfunction "PWRGD_5") (pintype "passive"))
    )
    (net (code "67") (name "unconnected-(RF0-NC-Pad9)") (class "Default")
      (node (ref "RF0") (pin "9") (pinfunction "NC_9") (pintype "bidirectional"))
    )
  )
)
